# Schematics.net
KiCad netlist of a schematic drawn in Altium Designer
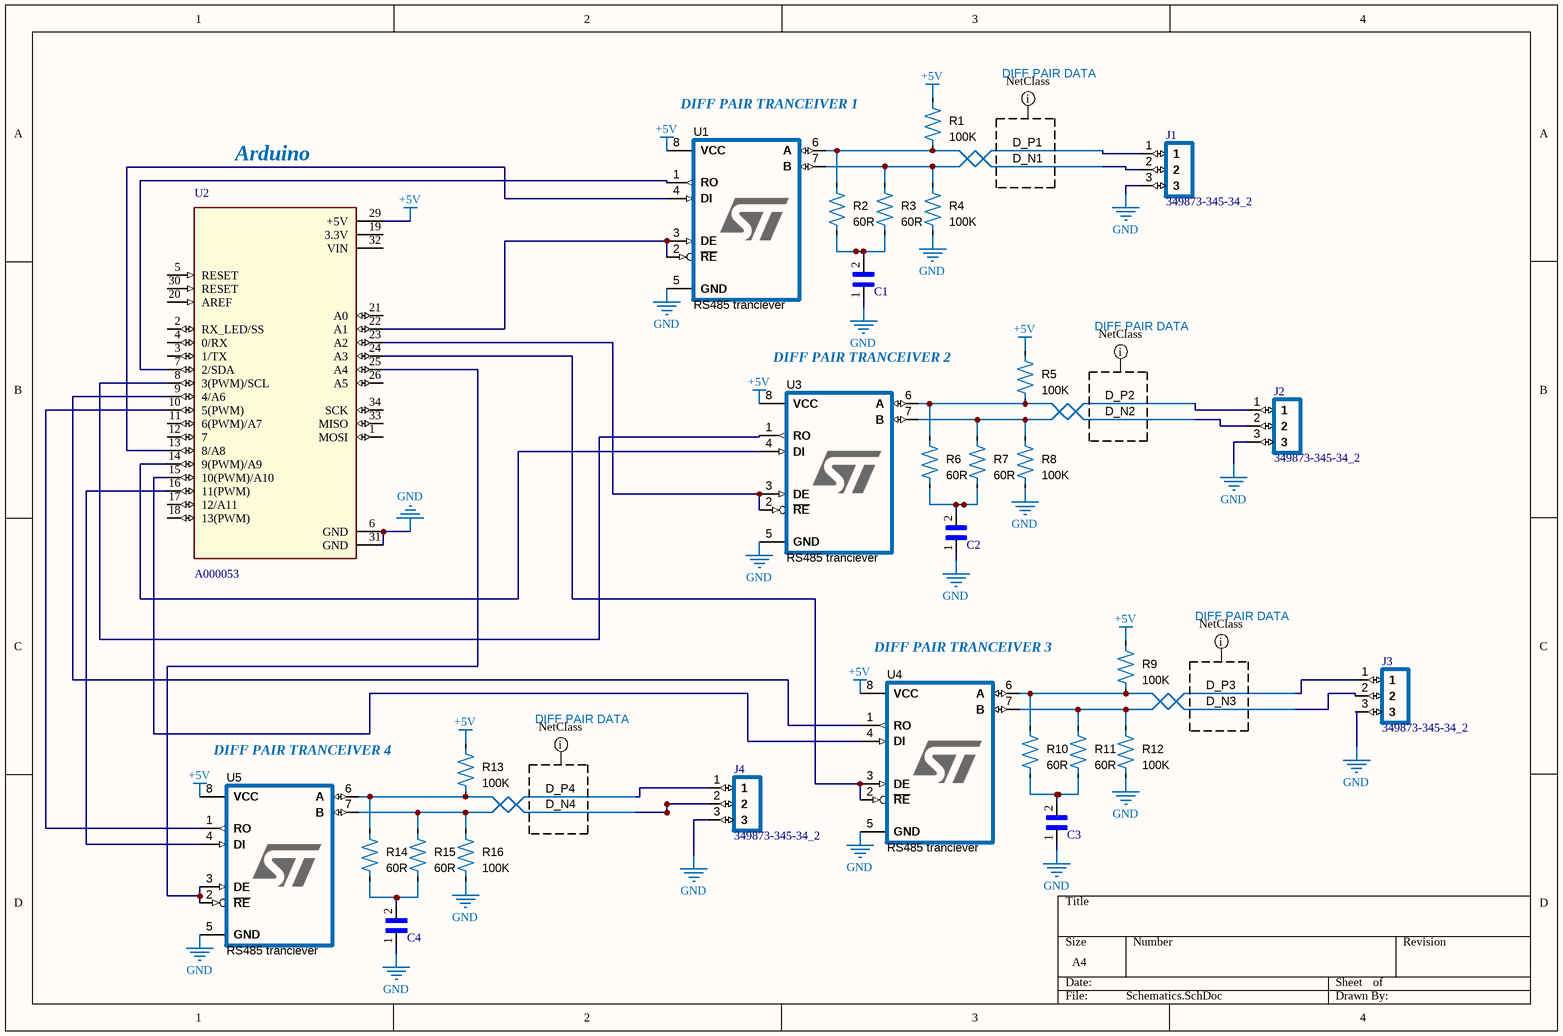
[diagram p0: Schematics.SchDoc]

(export (version "E")
  (design (tool "Eeschema 10.0.6"))
  (components
    (comp (ref "C1")
      (value "06035C104K4Z2A")
      (footprint "1608[0603]")
      (description "0.1ÂµF Â±10% 50V Ceramic Capacitor X7R 0603 _1608 Metric_")
      (fields (field (name "MF") "AVX") (field (name "DIGI-KEY_PART_NUMBER") "478-6344-1-ND"))
      (libsource (lib "Microcontrollers") (part "06035C104K4Z2A"))
    )
    (comp (ref "C2")
      (value "06035C104K4Z2A")
      (footprint "Miscellaneous Devices:1608[0603]")
      (description "0.1ÂµF Â±10% 50V Ceramic Capacitor X7R 0603 _1608 Metric_")
      (fields (field (name "MF") "AVX") (field (name "DIGI-KEY_PART_NUMBER") "478-6344-1-ND"))
      (libsource (lib "SnapEDAsch") (part "06035C104K4Z2A"))
    )
    (comp (ref "C3")
      (value "06035C104K4Z2A")
      (footprint "Miscellaneous Devices:1608[0603]")
      (description "0.1ÂµF Â±10% 50V Ceramic Capacitor X7R 0603 _1608 Metric_")
      (fields (field (name "MF") "AVX") (field (name "DIGI-KEY_PART_NUMBER") "478-6344-1-ND"))
      (libsource (lib "SnapEDAsch") (part "06035C104K4Z2A"))
    )
    (comp (ref "C4")
      (value "06035C104K4Z2A")
      (footprint "Miscellaneous Devices:1608[0603]")
      (description "0.1ÂµF Â±10% 50V Ceramic Capacitor X7R 0603 _1608 Metric_")
      (fields (field (name "MF") "AVX") (field (name "DIGI-KEY_PART_NUMBER") "478-6344-1-ND"))
      (libsource (lib "SnapEDAsch") (part "06035C104K4Z2A"))
    )
    (comp (ref "J1")
      (value "349873-345-34_2")
      (footprint "Header 1x3 male")
      (description "Header 1x3 male 2.54mm")
      (libsource (lib "Connectors") (part "349873-345-34_2"))
    )
    (comp (ref "J2")
      (value "349873-345-34_2")
      (footprint "Header 1x3 male")
      (description "Header 1x3 male 2.54mm")
      (libsource (lib "Connectors") (part "349873-345-34_2"))
    )
    (comp (ref "J3")
      (value "349873-345-34_2")
      (footprint "Header 1x3 male")
      (description "Header 1x3 male 2.54mm")
      (libsource (lib "Connectors") (part "349873-345-34_2"))
    )
    (comp (ref "J4")
      (value "349873-345-34_2")
      (footprint "Header 1x3 male")
      (description "Header 1x3 male 2.54mm")
      (libsource (lib "Connectors") (part "349873-345-34_2"))
    )
    (comp (ref "R1")
      (value "100K")
      (footprint "R0603")
      (description "R0603")
      (fields (field (name "Comment") "CPF-A-0603B100KE1"))
      (libsource (lib "Passive components") (part "CPF-A-0603B100KE1"))
    )
    (comp (ref "R2")
      (value "60R")
      (footprint "R0603")
      (description "R0603")
      (fields (field (name "Comment") "CPF-A-0603B100KE1"))
      (libsource (lib "Passive components") (part "CPF-A-0603B100KE1"))
    )
    (comp (ref "R3")
      (value "60R")
      (footprint "R0603")
      (description "R0603")
      (fields (field (name "Comment") "CPF-A-0603B100KE1"))
      (libsource (lib "Passive components") (part "CPF-A-0603B100KE1"))
    )
    (comp (ref "R4")
      (value "100K")
      (footprint "R0603")
      (description "R0603")
      (fields (field (name "Comment") "CPF-A-0603B100KE1"))
      (libsource (lib "Passive components") (part "CPF-A-0603B100KE1"))
    )
    (comp (ref "R5")
      (value "100K")
      (footprint "R0603")
      (description "R0603")
      (fields (field (name "Comment") "CPF-A-0603B100KE1"))
      (libsource (lib "Passive components") (part "CPF-A-0603B100KE1"))
    )
    (comp (ref "R6")
      (value "60R")
      (footprint "R0603")
      (description "R0603")
      (fields (field (name "Comment") "CPF-A-0603B100KE1"))
      (libsource (lib "Passive components") (part "CPF-A-0603B100KE1"))
    )
    (comp (ref "R7")
      (value "60R")
      (footprint "R0603")
      (description "R0603")
      (fields (field (name "Comment") "CPF-A-0603B100KE1"))
      (libsource (lib "Passive components") (part "CPF-A-0603B100KE1"))
    )
    (comp (ref "R8")
      (value "100K")
      (footprint "R0603")
      (description "R0603")
      (fields (field (name "Comment") "CPF-A-0603B100KE1"))
      (libsource (lib "Passive components") (part "CPF-A-0603B100KE1"))
    )
    (comp (ref "R9")
      (value "100K")
      (footprint "R0603")
      (description "R0603")
      (fields (field (name "Comment") "CPF-A-0603B100KE1"))
      (libsource (lib "Passive components") (part "CPF-A-0603B100KE1"))
    )
    (comp (ref "R10")
      (value "60R")
      (footprint "R0603")
      (description "R0603")
      (fields (field (name "Comment") "CPF-A-0603B100KE1"))
      (libsource (lib "Passive components") (part "CPF-A-0603B100KE1"))
    )
    (comp (ref "R11")
      (value "60R")
      (footprint "R0603")
      (description "R0603")
      (fields (field (name "Comment") "CPF-A-0603B100KE1"))
      (libsource (lib "Passive components") (part "CPF-A-0603B100KE1"))
    )
    (comp (ref "R12")
      (value "100K")
      (footprint "R0603")
      (description "R0603")
      (fields (field (name "Comment") "CPF-A-0603B100KE1"))
      (libsource (lib "Passive components") (part "CPF-A-0603B100KE1"))
    )
    (comp (ref "R13")
      (value "100K")
      (footprint "R0603")
      (description "R0603")
      (fields (field (name "Comment") "CPF-A-0603B100KE1"))
      (libsource (lib "Passive components") (part "CPF-A-0603B100KE1"))
    )
    (comp (ref "R14")
      (value "60R")
      (footprint "R0603")
      (description "R0603")
      (fields (field (name "Comment") "CPF-A-0603B100KE1"))
      (libsource (lib "Passive components") (part "CPF-A-0603B100KE1"))
    )
    (comp (ref "R15")
      (value "60R")
      (footprint "R0603")
      (description "R0603")
      (fields (field (name "Comment") "CPF-A-0603B100KE1"))
      (libsource (lib "Passive components") (part "CPF-A-0603B100KE1"))
    )
    (comp (ref "R16")
      (value "100K")
      (footprint "R0603")
      (description "R0603")
      (fields (field (name "Comment") "CPF-A-0603B100KE1"))
      (libsource (lib "Passive components") (part "CPF-A-0603B100KE1"))
    )
    (comp (ref "U1")
      (value "RS485 tranciever")
      (footprint "ST485CDR")
      (description "RS485 tranciever single")
      (libsource (lib "IC") (part "ST485CDR"))
    )
    (comp (ref "U2")
      (value "A000053")
      (footprint "*ARDUINO_A000053")
      (description "MCU, ARDUINO MICRO, LEONARDO BASED, ATMEGA32u4, 5V, USB-MICRO")
      (fields (field (name "MF") "Arduino"))
      (libsource (lib "Schlib") (part "A000053"))
    )
    (comp (ref "U3")
      (value "RS485 tranciever")
      (footprint "ST485CDR")
      (description "RS485 tranciever single")
      (libsource (lib "IC") (part "ST485CDR"))
    )
    (comp (ref "U4")
      (value "RS485 tranciever")
      (footprint "ST485CDR")
      (description "RS485 tranciever single")
      (libsource (lib "IC") (part "ST485CDR"))
    )
    (comp (ref "U5")
      (value "RS485 tranciever")
      (footprint "ST485CDR")
      (description "RS485 tranciever single")
      (libsource (lib "IC") (part "ST485CDR"))
    )
  )
  (nets
    (net (code "1") (name "+5V") (class "Default")
      (node (ref "R1") (pin "2") (pinfunction "2_2") (pintype "passive"))
      (node (ref "R13") (pin "2") (pinfunction "2_2") (pintype "passive"))
      (node (ref "R5") (pin "2") (pinfunction "2_2") (pintype "passive"))
      (node (ref "R9") (pin "2") (pinfunction "2_2") (pintype "passive"))
      (node (ref "U1") (pin "8") (pinfunction "VCC_8") (pintype "power_in"))
      (node (ref "U2") (pin "29") (pinfunction "+5V_29") (pintype "power_in"))
      (node (ref "U3") (pin "8") (pinfunction "VCC_8") (pintype "power_in"))
      (node (ref "U4") (pin "8") (pinfunction "VCC_8") (pintype "power_in"))
      (node (ref "U5") (pin "8") (pinfunction "VCC_8") (pintype "power_in"))
    )
    (net (code "2") (name "/D_N1") (class "Default")
      (node (ref "J1") (pin "2") (pinfunction "2_2") (pintype "bidirectional"))
      (node (ref "R3") (pin "2") (pinfunction "2_2") (pintype "passive"))
      (node (ref "R4") (pin "2") (pinfunction "2_2") (pintype "passive"))
      (node (ref "U1") (pin "7") (pinfunction "B_7") (pintype "bidirectional"))
    )
    (net (code "3") (name "/D_N2") (class "Default")
      (node (ref "J2") (pin "2") (pinfunction "2_2") (pintype "bidirectional"))
      (node (ref "R7") (pin "2") (pinfunction "2_2") (pintype "passive"))
      (node (ref "R8") (pin "2") (pinfunction "2_2") (pintype "passive"))
      (node (ref "U3") (pin "7") (pinfunction "B_7") (pintype "bidirectional"))
    )
    (net (code "4") (name "/D_N3") (class "Default")
      (node (ref "J3") (pin "2") (pinfunction "2_2") (pintype "bidirectional"))
      (node (ref "R11") (pin "2") (pinfunction "2_2") (pintype "passive"))
      (node (ref "R12") (pin "2") (pinfunction "2_2") (pintype "passive"))
      (node (ref "U4") (pin "7") (pinfunction "B_7") (pintype "bidirectional"))
    )
    (net (code "5") (name "/D_N4") (class "Default")
      (node (ref "J4") (pin "2") (pinfunction "2_2") (pintype "bidirectional"))
      (node (ref "R15") (pin "2") (pinfunction "2_2") (pintype "passive"))
      (node (ref "R16") (pin "2") (pinfunction "2_2") (pintype "passive"))
      (node (ref "U5") (pin "7") (pinfunction "B_7") (pintype "bidirectional"))
    )
    (net (code "6") (name "/D_P1") (class "Default")
      (node (ref "J1") (pin "1") (pinfunction "1_1") (pintype "bidirectional"))
      (node (ref "R1") (pin "1") (pinfunction "1_1") (pintype "passive"))
      (node (ref "R2") (pin "2") (pinfunction "2_2") (pintype "passive"))
      (node (ref "U1") (pin "6") (pinfunction "A_6") (pintype "bidirectional"))
    )
    (net (code "7") (name "/D_P2") (class "Default")
      (node (ref "J2") (pin "1") (pinfunction "1_1") (pintype "bidirectional"))
      (node (ref "R5") (pin "1") (pinfunction "1_1") (pintype "passive"))
      (node (ref "R6") (pin "2") (pinfunction "2_2") (pintype "passive"))
      (node (ref "U3") (pin "6") (pinfunction "A_6") (pintype "bidirectional"))
    )
    (net (code "8") (name "/D_P3") (class "Default")
      (node (ref "J3") (pin "1") (pinfunction "1_1") (pintype "bidirectional"))
      (node (ref "R10") (pin "2") (pinfunction "2_2") (pintype "passive"))
      (node (ref "R9") (pin "1") (pinfunction "1_1") (pintype "passive"))
      (node (ref "U4") (pin "6") (pinfunction "A_6") (pintype "bidirectional"))
    )
    (net (code "9") (name "/D_P4") (class "Default")
      (node (ref "J4") (pin "1") (pinfunction "1_1") (pintype "bidirectional"))
      (node (ref "R13") (pin "1") (pinfunction "1_1") (pintype "passive"))
      (node (ref "R14") (pin "2") (pinfunction "2_2") (pintype "passive"))
      (node (ref "U5") (pin "6") (pinfunction "A_6") (pintype "bidirectional"))
    )
    (net (code "10") (name "GND") (class "Default")
      (node (ref "C1") (pin "1") (pinfunction "1_1") (pintype "passive"))
      (node (ref "C2") (pin "1") (pinfunction "1_1") (pintype "passive"))
      (node (ref "C3") (pin "1") (pinfunction "1_1") (pintype "passive"))
      (node (ref "C4") (pin "1") (pinfunction "1_1") (pintype "passive"))
      (node (ref "J1") (pin "3") (pinfunction "3_3") (pintype "bidirectional"))
      (node (ref "J2") (pin "3") (pinfunction "3_3") (pintype "bidirectional"))
      (node (ref "J3") (pin "3") (pinfunction "3_3") (pintype "bidirectional"))
      (node (ref "J4") (pin "3") (pinfunction "3_3") (pintype "bidirectional"))
      (node (ref "R12") (pin "1") (pinfunction "1_1") (pintype "passive"))
      (node (ref "R16") (pin "1") (pinfunction "1_1") (pintype "passive"))
      (node (ref "R4") (pin "1") (pinfunction "1_1") (pintype "passive"))
      (node (ref "R8") (pin "1") (pinfunction "1_1") (pintype "passive"))
      (node (ref "U1") (pin "5") (pinfunction "GND_5") (pintype "power_in"))
      (node (ref "U2") (pin "31") (pinfunction "GND_31") (pintype "power_in"))
      (node (ref "U2") (pin "6") (pinfunction "GND_6") (pintype "power_in"))
      (node (ref "U3") (pin "5") (pinfunction "GND_5") (pintype "power_in"))
      (node (ref "U4") (pin "5") (pinfunction "GND_5") (pintype "power_in"))
      (node (ref "U5") (pin "5") (pinfunction "GND_5") (pintype "power_in"))
    )
    (net (code "11") (name "Net-(C1-Pad2)") (class "Default")
      (node (ref "C1") (pin "2") (pinfunction "2_2") (pintype "passive"))
      (node (ref "R2") (pin "1") (pinfunction "1_1") (pintype "passive"))
      (node (ref "R3") (pin "1") (pinfunction "1_1") (pintype "passive"))
    )
    (net (code "12") (name "Net-(C2-Pad2)") (class "Default")
      (node (ref "C2") (pin "2") (pinfunction "2_2") (pintype "passive"))
      (node (ref "R6") (pin "1") (pinfunction "1_1") (pintype "passive"))
      (node (ref "R7") (pin "1") (pinfunction "1_1") (pintype "passive"))
    )
    (net (code "13") (name "Net-(C3-Pad2)") (class "Default")
      (node (ref "C3") (pin "2") (pinfunction "2_2") (pintype "passive"))
      (node (ref "R10") (pin "1") (pinfunction "1_1") (pintype "passive"))
      (node (ref "R11") (pin "1") (pinfunction "1_1") (pintype "passive"))
    )
    (net (code "14") (name "Net-(C4-Pad2)") (class "Default")
      (node (ref "C4") (pin "2") (pinfunction "2_2") (pintype "passive"))
      (node (ref "R14") (pin "1") (pinfunction "1_1") (pintype "passive"))
      (node (ref "R15") (pin "1") (pinfunction "1_1") (pintype "passive"))
    )
    (net (code "15") (name "Net-(U1-DE)") (class "Default")
      (node (ref "U1") (pin "2") (pinfunction "~{RE}_2") (pintype "input"))
      (node (ref "U1") (pin "3") (pinfunction "DE_3") (pintype "input"))
      (node (ref "U2") (pin "22") (pinfunction "A1_22") (pintype "bidirectional"))
    )
    (net (code "16") (name "Net-(U1-DI)") (class "Default")
      (node (ref "U1") (pin "4") (pinfunction "DI_4") (pintype "input"))
      (node (ref "U2") (pin "13") (pinfunction "8/A8_13") (pintype "bidirectional"))
    )
    (net (code "17") (name "Net-(U1-RO)") (class "Default")
      (node (ref "U1") (pin "1") (pinfunction "RO_1") (pintype "output"))
      (node (ref "U2") (pin "7") (pinfunction "2/SDA_7") (pintype "bidirectional"))
    )
    (net (code "18") (name "Net-(U2-3(PWM){slash}SCL)") (class "Default")
      (node (ref "U2") (pin "8") (pinfunction "3(PWM)/SCL_8") (pintype "bidirectional"))
      (node (ref "U3") (pin "1") (pinfunction "RO_1") (pintype "output"))
    )
    (net (code "19") (name "Net-(U2-4{slash}A6)") (class "Default")
      (node (ref "U2") (pin "9") (pinfunction "4/A6_9") (pintype "bidirectional"))
      (node (ref "U4") (pin "1") (pinfunction "RO_1") (pintype "output"))
    )
    (net (code "20") (name "Net-(U2-5(PWM))") (class "Default")
      (node (ref "U2") (pin "10") (pinfunction "5(PWM)_10") (pintype "bidirectional"))
      (node (ref "U5") (pin "1") (pinfunction "RO_1") (pintype "output"))
    )
    (net (code "21") (name "Net-(U2-9(PWM){slash}A9)") (class "Default")
      (node (ref "U2") (pin "14") (pinfunction "9(PWM)/A9_14") (pintype "bidirectional"))
      (node (ref "U3") (pin "4") (pinfunction "DI_4") (pintype "input"))
    )
    (net (code "22") (name "Net-(U2-10(PWM){slash}A10)") (class "Default")
      (node (ref "U2") (pin "15") (pinfunction "10(PWM)/A10_15") (pintype "bidirectional"))
      (node (ref "U4") (pin "4") (pinfunction "DI_4") (pintype "input"))
    )
    (net (code "23") (name "Net-(U2-11(PWM))") (class "Default")
      (node (ref "U2") (pin "16") (pinfunction "11(PWM)_16") (pintype "bidirectional"))
      (node (ref "U5") (pin "4") (pinfunction "DI_4") (pintype "input"))
    )
    (net (code "24") (name "Net-(U2-A2)") (class "Default")
      (node (ref "U2") (pin "23") (pinfunction "A2_23") (pintype "bidirectional"))
      (node (ref "U3") (pin "2") (pinfunction "~{RE}_2") (pintype "input"))
      (node (ref "U3") (pin "3") (pinfunction "DE_3") (pintype "input"))
    )
    (net (code "25") (name "Net-(U2-A3)") (class "Default")
      (node (ref "U2") (pin "24") (pinfunction "A3_24") (pintype "bidirectional"))
      (node (ref "U4") (pin "2") (pinfunction "~{RE}_2") (pintype "input"))
      (node (ref "U4") (pin "3") (pinfunction "DE_3") (pintype "input"))
    )
    (net (code "26") (name "Net-(U2-A4)") (class "Default")
      (node (ref "U2") (pin "25") (pinfunction "A4_25") (pintype "bidirectional"))
      (node (ref "U5") (pin "2") (pinfunction "~{RE}_2") (pintype "input"))
      (node (ref "U5") (pin "3") (pinfunction "DE_3") (pintype "input"))
    )
    (net (code "27") (name "unconnected-(U2-0{slash}RX-Pad4)") (class "Default")
      (node (ref "U2") (pin "4") (pinfunction "0/RX_4") (pintype "bidirectional"))
    )
    (net (code "28") (name "unconnected-(U2-1{slash}TX-Pad3)") (class "Default")
      (node (ref "U2") (pin "3") (pinfunction "1/TX_3") (pintype "bidirectional"))
    )
    (net (code "29") (name "unconnected-(U2-3.3V-Pad19)") (class "Default")
      (node (ref "U2") (pin "19") (pinfunction "3.3V_19") (pintype "power_in"))
    )
    (net (code "30") (name "unconnected-(U2-6(PWM){slash}A7-Pad11)") (class "Default")
      (node (ref "U2") (pin "11") (pinfunction "6(PWM)/A7_11") (pintype "bidirectional"))
    )
    (net (code "31") (name "unconnected-(U2-7-Pad12)") (class "Default")
      (node (ref "U2") (pin "12") (pinfunction "7_12") (pintype "bidirectional"))
    )
    (net (code "32") (name "unconnected-(U2-12{slash}A11-Pad17)") (class "Default")
      (node (ref "U2") (pin "17") (pinfunction "12/A11_17") (pintype "bidirectional"))
    )
    (net (code "33") (name "unconnected-(U2-13(PWM)-Pad18)") (class "Default")
      (node (ref "U2") (pin "18") (pinfunction "13(PWM)_18") (pintype "bidirectional"))
    )
    (net (code "34") (name "unconnected-(U2-A0-Pad21)") (class "Default")
      (node (ref "U2") (pin "21") (pinfunction "A0_21") (pintype "bidirectional"))
    )
    (net (code "35") (name "unconnected-(U2-A5-Pad26)") (class "Default")
      (node (ref "U2") (pin "26") (pinfunction "A5_26") (pintype "bidirectional"))
    )
    (net (code "36") (name "unconnected-(U2-AREF-Pad20)") (class "Default")
      (node (ref "U2") (pin "20") (pinfunction "AREF_20") (pintype "input"))
    )
    (net (code "37") (name "unconnected-(U2-MISO-Pad33)") (class "Default")
      (node (ref "U2") (pin "33") (pinfunction "MISO_33") (pintype "bidirectional"))
    )
    (net (code "38") (name "unconnected-(U2-MOSI-Pad1)") (class "Default")
      (node (ref "U2") (pin "1") (pinfunction "MOSI_1") (pintype "bidirectional"))
    )
    (net (code "39") (name "unconnected-(U2-RESET-Pad5)") (class "Default")
      (node (ref "U2") (pin "5") (pinfunction "RESET_5") (pintype "input"))
    )
    (net (code "40") (name "unconnected-(U2-RESET-Pad30)") (class "Default")
      (node (ref "U2") (pin "30") (pinfunction "RESET_30") (pintype "input"))
    )
    (net (code "41") (name "unconnected-(U2-RX_LED{slash}SS-Pad2)") (class "Default")
      (node (ref "U2") (pin "2") (pinfunction "RX_LED/SS_2") (pintype "bidirectional"))
    )
    (net (code "42") (name "unconnected-(U2-SCK-Pad34)") (class "Default")
      (node (ref "U2") (pin "34") (pinfunction "SCK_34") (pintype "bidirectional"))
    )
    (net (code "43") (name "unconnected-(U2-VIN-Pad32)") (class "Default")
      (node (ref "U2") (pin "32") (pinfunction "VIN_32") (pintype "power_in"))
    )
  )
)
